# LTC2990_Breakout.net
KiCad netlist of a schematic drawn in Altium Designer
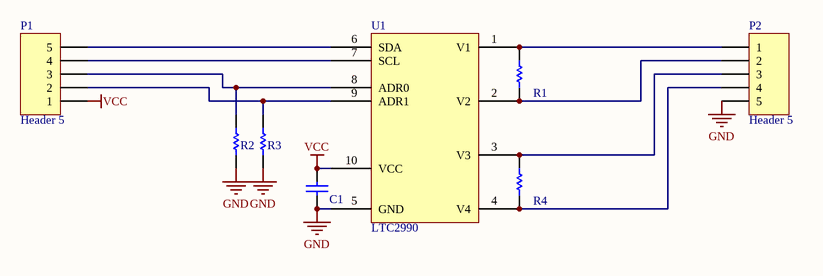
[diagram p0: LTC2990 Breakout.SchDoc]

(export (version "E")
  (design (tool "Eeschema 10.0.6"))
  (components
    (comp (ref "C1")
      (value "CAP 1uF 35V 0805(2012)")
      (footprint "CAPC0805(2012)145_N")
      (description "CAP 1uF 35V ±10% 0805 (2012 Metric) Thickness 1.45mm SMD")
      (fields (field (name "TOLERANCE") "±10%"))
      (libsource (lib "Altium Content Vault") (part "CAP"))
    )
    (comp (ref "P1")
      (value "Header 5")
      (footprint "HDR1X5")
      (description "Header, 5-Pin")
      (fields (field (name "PUBLISHER") "Altium Limited"))
      (libsource (lib "Miscellaneous Connectors") (part "Header 5"))
    )
    (comp (ref "P2")
      (value "Header 5")
      (footprint "HDR1X5")
      (description "Header, 5-Pin")
      (fields (field (name "PUBLISHER") "Altium Limited"))
      (libsource (lib "") (part "Header 5_1"))
    )
    (comp (ref "R1")
      (value "1R 5% 0805(2012)")
      (footprint "RESC0805(2012)_M")
      (description "1R 0.125W 5% 0805 (2012 Metric)  SMD")
      (fields (field (name "POWER") "0.125 W") (field (name "TOLERANCE") "5 %"))
      (libsource (lib "Altium Content Vault") (part "RES"))
    )
    (comp (ref "R2")
      (value "10K 5% 0805(2012)")
      (footprint "RESC0805(2012)_N")
      (description "10K 0.125W 5% 0805 (2012 Metric)  SMD")
      (fields (field (name "POWER") "0.125 W") (field (name "TOLERANCE") "5 %"))
      (libsource (lib "Altium Content Vault") (part "RES"))
    )
    (comp (ref "R3")
      (value "10K 5% 0805(2012)")
      (footprint "RESC0805(2012)_N")
      (description "10K 0.125W 5% 0805 (2012 Metric)  SMD")
      (fields (field (name "POWER") "0.125 W") (field (name "TOLERANCE") "5 %"))
      (libsource (lib "Altium Content Vault") (part "RES"))
    )
    (comp (ref "R4")
      (value "1R 5% 0805(2012)")
      (footprint "RESC0805(2012)_M")
      (description "1R 0.125W 5% 0805 (2012 Metric)  SMD")
      (fields (field (name "POWER") "0.125 W") (field (name "TOLERANCE") "5 %"))
      (libsource (lib "Altium Content Vault") (part "RES"))
    )
    (comp (ref "U1")
      (value "LTC2990")
      (footprint "LT-MS 10-MSOP")
      (description "Quad I2C Voltage, Current and Temperature Monitor")
      (libsource (lib "LTC2990") (part "LTC2990"))
    )
  )
  (nets
    (net (code "1") (name "GND") (class "Default")
      (node (ref "C1") (pin "1") (pinfunction "1_1") (pintype "passive"))
      (node (ref "P2") (pin "5") (pinfunction "5_5") (pintype "passive"))
      (node (ref "R2") (pin "2") (pinfunction "2_2") (pintype "passive"))
      (node (ref "R3") (pin "2") (pinfunction "2_2") (pintype "passive"))
      (node (ref "U1") (pin "5") (pinfunction "GND_5") (pintype "passive"))
    )
    (net (code "2") (name "Net-(U1-ADR0)") (class "Default")
      (node (ref "P1") (pin "3") (pinfunction "3_3") (pintype "passive"))
      (node (ref "R2") (pin "1") (pinfunction "1_1") (pintype "passive"))
      (node (ref "U1") (pin "8") (pinfunction "ADR0_8") (pintype "passive"))
    )
    (net (code "3") (name "Net-(U1-ADR1)") (class "Default")
      (node (ref "P1") (pin "2") (pinfunction "2_2") (pintype "passive"))
      (node (ref "R3") (pin "1") (pinfunction "1_1") (pintype "passive"))
      (node (ref "U1") (pin "9") (pinfunction "ADR1_9") (pintype "passive"))
    )
    (net (code "4") (name "Net-(U1-SCL)") (class "Default")
      (node (ref "P1") (pin "4") (pinfunction "4_4") (pintype "passive"))
      (node (ref "U1") (pin "7") (pinfunction "SCL_7") (pintype "passive"))
    )
    (net (code "5") (name "Net-(U1-SDA)") (class "Default")
      (node (ref "P1") (pin "5") (pinfunction "5_5") (pintype "passive"))
      (node (ref "U1") (pin "6") (pinfunction "SDA_6") (pintype "passive"))
    )
    (net (code "6") (name "Net-(U1-V1)") (class "Default")
      (node (ref "P2") (pin "1") (pinfunction "1_1") (pintype "passive"))
      (node (ref "R1") (pin "2") (pinfunction "2_2") (pintype "passive"))
      (node (ref "U1") (pin "1") (pinfunction "V1_1") (pintype "passive"))
    )
    (net (code "7") (name "Net-(U1-V2)") (class "Default")
      (node (ref "P2") (pin "2") (pinfunction "2_2") (pintype "passive"))
      (node (ref "R1") (pin "1") (pinfunction "1_1") (pintype "passive"))
      (node (ref "U1") (pin "2") (pinfunction "V2_2") (pintype "passive"))
    )
    (net (code "8") (name "Net-(U1-V3)") (class "Default")
      (node (ref "P2") (pin "3") (pinfunction "3_3") (pintype "passive"))
      (node (ref "R4") (pin "2") (pinfunction "2_2") (pintype "passive"))
      (node (ref "U1") (pin "3") (pinfunction "V3_3") (pintype "passive"))
    )
    (net (code "9") (name "Net-(U1-V4)") (class "Default")
      (node (ref "P2") (pin "4") (pinfunction "4_4") (pintype "passive"))
      (node (ref "R4") (pin "1") (pinfunction "1_1") (pintype "passive"))
      (node (ref "U1") (pin "4") (pinfunction "V4_4") (pintype "passive"))
    )
    (net (code "10") (name "VCC") (class "Default")
      (node (ref "C1") (pin "2") (pinfunction "2_2") (pintype "passive"))
      (node (ref "P1") (pin "1") (pinfunction "1_1") (pintype "passive"))
      (node (ref "U1") (pin "10") (pinfunction "VCC_10") (pintype "passive"))
    )
  )
)
